# MCU_Control.net
KiCad netlist of a schematic drawn in Altium Designer
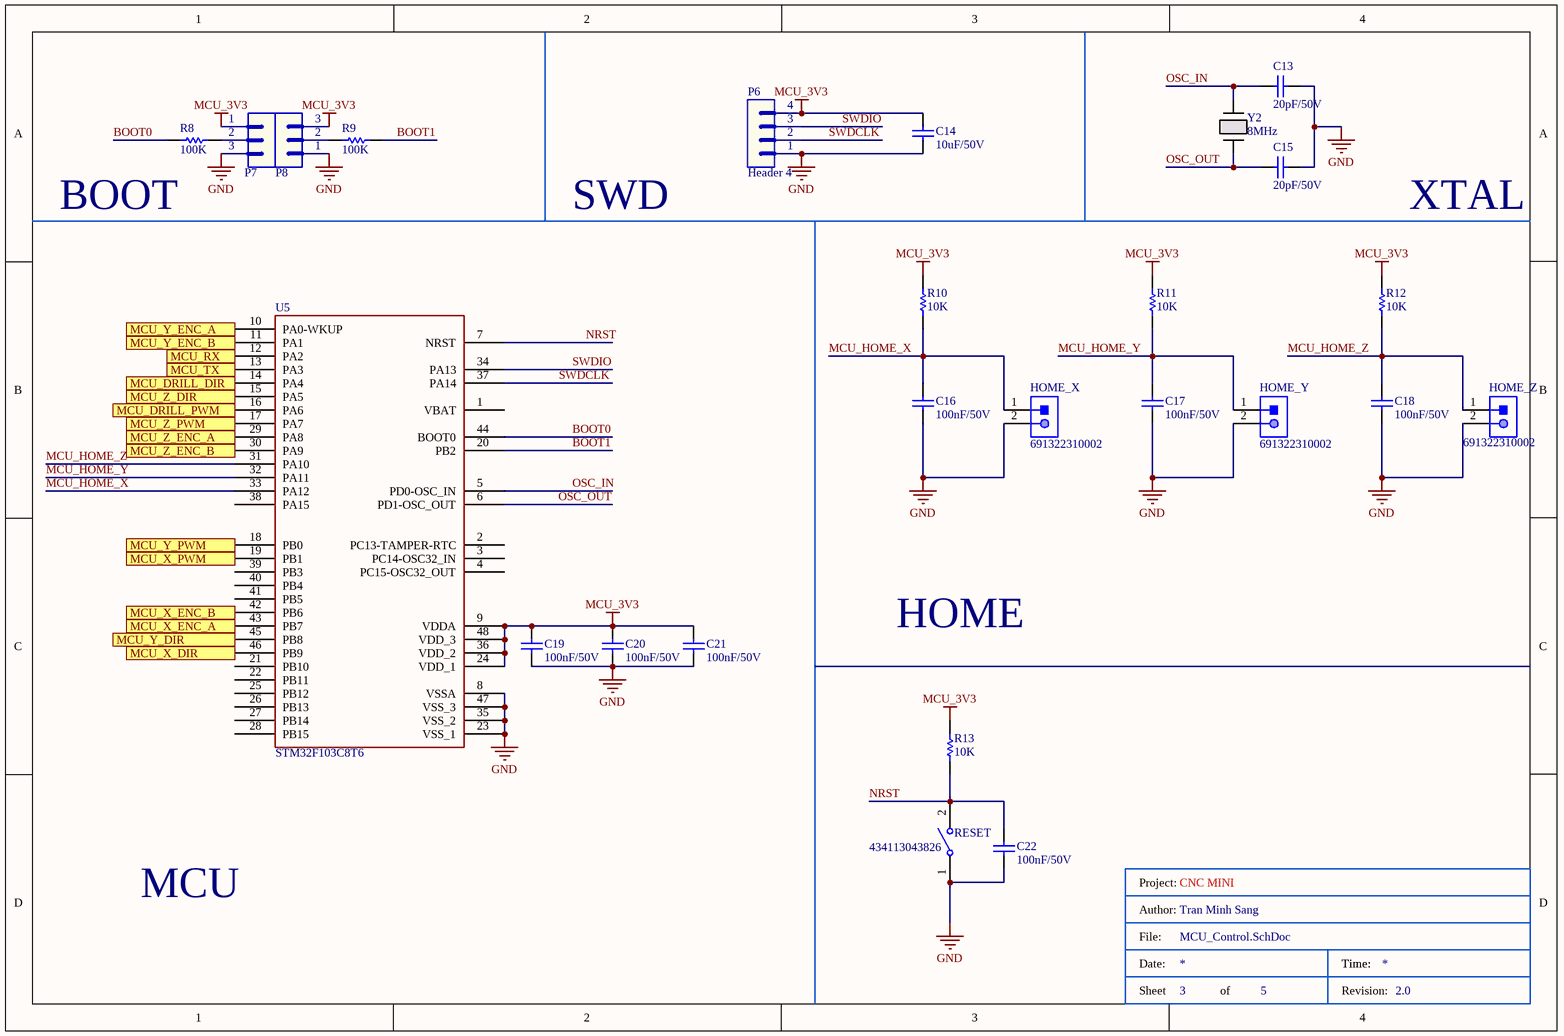
[diagram p0: MCU_Control.SchDoc]

(export (version "E")
  (design (tool "Eeschema 10.0.6"))
  (components
    (comp (ref "C13")
      (value "20pF/50V")
      (footprint "CAP-SM-0805")
      (description "CAP CER 22PF 100V X7R 0805")
      (fields
        (field (name "MANUFACTURER") "Johanson Dielectrics Inc.")
        (field (name "MANUFACTURER PART NUMBER") "101X15W102MV4E")
      )
      (libsource (lib "capacitor-smd") (part "Cap-22pF-50V-0805"))
    )
    (comp (ref "C14")
      (value "10uF/50V")
      (footprint "CAP-SM-0805")
      (description "CAP CER 10UF 50V X5R 0805")
      (fields
        (field (name "MANUFACTURER") "Yageo")
        (field (name "MANUFACTURER PART NUMBER") "CC0805KKX5R9BB106")
      )
      (libsource (lib "capacitor-smd") (part "Cap-10uF-50V-0805"))
    )
    (comp (ref "C15")
      (value "20pF/50V")
      (footprint "CAP-SM-0805")
      (description "CAP CER 22PF 100V X7R 0805")
      (fields
        (field (name "MANUFACTURER") "Johanson Dielectrics Inc.")
        (field (name "MANUFACTURER PART NUMBER") "101X15W102MV4E")
      )
      (libsource (lib "capacitor-smd") (part "Cap-22pF-50V-0805"))
    )
    (comp (ref "C16")
      (value "100nF/50V")
      (footprint "CAP-SM-0805")
      (description "CAP CER 0.1UF 50V Y5V 0805")
      (fields
        (field (name "MANUFACTURER") "Samsung Electro-Mechanics")
        (field (name "MANUFACTURER PART NUMBER") "CL21F104ZBCNNNC")
      )
      (libsource (lib "capacitor-smd") (part "Cap-100nF-50V-0805"))
    )
    (comp (ref "C17")
      (value "100nF/50V")
      (footprint "CAP-SM-0805")
      (description "CAP CER 0.1UF 50V Y5V 0805")
      (fields
        (field (name "MANUFACTURER") "Samsung Electro-Mechanics")
        (field (name "MANUFACTURER PART NUMBER") "CL21F104ZBCNNNC")
      )
      (libsource (lib "capacitor-smd") (part "Cap-100nF-50V-0805"))
    )
    (comp (ref "C18")
      (value "100nF/50V")
      (footprint "CAP-SM-0805")
      (description "CAP CER 0.1UF 50V Y5V 0805")
      (fields
        (field (name "MANUFACTURER") "Samsung Electro-Mechanics")
        (field (name "MANUFACTURER PART NUMBER") "CL21F104ZBCNNNC")
      )
      (libsource (lib "capacitor-smd") (part "Cap-100nF-50V-0805"))
    )
    (comp (ref "C19")
      (value "100nF/50V")
      (footprint "CAP-SM-0805")
      (description "CAP CER 0.1UF 50V Y5V 0805")
      (fields
        (field (name "MANUFACTURER") "Samsung Electro-Mechanics")
        (field (name "MANUFACTURER PART NUMBER") "CL21F104ZBCNNNC")
      )
      (libsource (lib "capacitor-smd") (part "Cap-100nF-50V-0805"))
    )
    (comp (ref "C20")
      (value "100nF/50V")
      (footprint "CAP-SM-0805")
      (description "CAP CER 0.1UF 50V Y5V 0805")
      (fields
        (field (name "MANUFACTURER") "Samsung Electro-Mechanics")
        (field (name "MANUFACTURER PART NUMBER") "CL21F104ZBCNNNC")
      )
      (libsource (lib "capacitor-smd") (part "Cap-100nF-50V-0805"))
    )
    (comp (ref "C21")
      (value "100nF/50V")
      (footprint "CAP-SM-0805")
      (description "CAP CER 0.1UF 50V Y5V 0805")
      (fields
        (field (name "MANUFACTURER") "Samsung Electro-Mechanics")
        (field (name "MANUFACTURER PART NUMBER") "CL21F104ZBCNNNC")
      )
      (libsource (lib "capacitor-smd") (part "Cap-100nF-50V-0805"))
    )
    (comp (ref "C22")
      (value "100nF/50V")
      (footprint "CAP-SM-0805")
      (description "CAP CER 0.1UF 50V Y5V 0805")
      (fields
        (field (name "MANUFACTURER") "Samsung Electro-Mechanics")
        (field (name "MANUFACTURER PART NUMBER") "CL21F104ZBCNNNC")
      )
      (libsource (lib "capacitor-smd") (part "Cap-100nF-50V-0805"))
    )
    (comp (ref "HOME_X")
      (value "691322310002")
      (footprint "691322310002")
      (description "WR-TBL Serie 322 Horizontal PCB Header, Pluggable, pitch 3.81mm, 2p")
      (fields (field (name "PUBLISHER") "Wurth Elektronik"))
      (libsource (lib "WR-TBL_Pluggable PCB Header") (part "691322310002"))
    )
    (comp (ref "HOME_Y")
      (value "691322310002")
      (footprint "691322310002")
      (description "WR-TBL Serie 322 Horizontal PCB Header, Pluggable, pitch 3.81mm, 2p")
      (fields (field (name "PUBLISHER") "Wurth Elektronik"))
      (libsource (lib "WR-TBL_Pluggable PCB Header") (part "691322310002"))
    )
    (comp (ref "HOME_Z")
      (value "691322310002")
      (footprint "691322310002")
      (description "WR-TBL Serie 322 Horizontal PCB Header, Pluggable, pitch 3.81mm, 2p")
      (fields (field (name "PUBLISHER") "Wurth Elektronik"))
      (libsource (lib "WR-TBL_Pluggable PCB Header") (part "691322310002"))
    )
    (comp (ref "P6")
      (value "Header 4")
      (footprint "JP4")
      (description "Header, 4-Pin")
      (fields (field (name "LOCAL SUPPLIER PART NUMBER") "x") (field (name "PUBLISHER") "Altium Limited"))
      (libsource (lib "header-connector") (part "Header 4"))
    )
    (comp (ref "P7")
      (value "Header 3")
      (footprint "JP3")
      (description "Header, 3-Pin")
      (fields (field (name "LOCAL SUPPLIER PART NUMBER") "x") (field (name "PUBLISHER") "Altium Limited"))
      (libsource (lib "header-connector") (part "Header 3"))
    )
    (comp (ref "P8")
      (value "Header 3")
      (footprint "JP3")
      (description "Header, 3-Pin")
      (fields (field (name "LOCAL SUPPLIER PART NUMBER") "x") (field (name "PUBLISHER") "Altium Limited"))
      (libsource (lib "") (part "Header 3_1"))
    )
    (comp (ref "R8")
      (value "100K")
      (footprint "resistor-smd:RES-SM-0805")
      (description "RES 0 OHM JUMPER 0805")
      (fields
        (field (name "MANUFACTURER") "Vishay Dale")
        (field (name "MANUFACTURER PART NUMBER") "WSL080500000ZEA9")
      )
      (libsource (lib "resistor-smd") (part "Res-100K-0805"))
    )
    (comp (ref "R9")
      (value "100K")
      (footprint "resistor-smd:RES-SM-0805")
      (description "RES 0 OHM JUMPER 0805")
      (fields
        (field (name "MANUFACTURER") "Vishay Dale")
        (field (name "MANUFACTURER PART NUMBER") "WSL080500000ZEA9")
      )
      (libsource (lib "resistor-smd") (part "Res-100K-0805"))
    )
    (comp (ref "R10")
      (value "10K")
      (footprint "resistor-smd:RES-SM-0805")
      (description "RES 10K OHM 1% 1/4W 0805")
      (fields
        (field (name "MANUFACTURER") "Stackpole Electronics Inc")
        (field (name "MANUFACTURER PART NUMBER") "RNCP0805FTD10K0")
      )
      (libsource (lib "resistor-smd") (part "Res-10k-0805"))
    )
    (comp (ref "R11")
      (value "10K")
      (footprint "resistor-smd:RES-SM-0805")
      (description "RES 10K OHM 1% 1/4W 0805")
      (fields
        (field (name "MANUFACTURER") "Stackpole Electronics Inc")
        (field (name "MANUFACTURER PART NUMBER") "RNCP0805FTD10K0")
      )
      (libsource (lib "resistor-smd") (part "Res-10k-0805"))
    )
    (comp (ref "R12")
      (value "10K")
      (footprint "resistor-smd:RES-SM-0805")
      (description "RES 10K OHM 1% 1/4W 0805")
      (fields
        (field (name "MANUFACTURER") "Stackpole Electronics Inc")
        (field (name "MANUFACTURER PART NUMBER") "RNCP0805FTD10K0")
      )
      (libsource (lib "resistor-smd") (part "Res-10k-0805"))
    )
    (comp (ref "R13")
      (value "10K")
      (footprint "resistor-smd:RES-SM-0805")
      (description "RES 10K OHM 1% 1/4W 0805")
      (fields
        (field (name "MANUFACTURER") "Stackpole Electronics Inc")
        (field (name "MANUFACTURER PART NUMBER") "RNCP0805FTD10K0")
      )
      (libsource (lib "resistor-smd") (part "Res-10k-0805"))
    )
    (comp (ref "RESET")
      (value "434113043826")
      (footprint "434113043826")
      (description "WS-TASV J-Bend SMT Tact Switch 6x3.5mm, height 4.3mm, 260gf")
      (fields (field (name "LOCAL SUPPLIER PART NUMBER") "x") (field (name "PUBLISHER") "Wurth Elektronik"))
      (libsource (lib "switch") (part "434113043826"))
    )
    (comp (ref "U5")
      (value "STM32F103C8T6")
      (footprint "LQFP-48")
      (fields (field (name "MANUFACTURER") "ST Electronic"))
      (libsource (lib "MiniCNC_ver2") (part "STM32F103C8T6"))
    )
    (comp (ref "Y2")
      (value "8MHz")
      (footprint "xtal2_CX5032GB_AVX-L")
      (description "No Description Available")
      (fields
        (field (name "MANUFACTURER_PART_NUMBER") "CX5032GB08000H0HEQZ1")
        (field (name "COPYRIGHT") "Copyright (C) 2023 Ultra Librarian. All rights reserved.")
      )
      (libsource (lib "MiniCNC_ver2") (part "XTAL"))
    )
  )
  (nets
    (net (code "1") (name "/BOOT0") (class "Default")
      (node (ref "R8") (pin "1") (pinfunction "1_1") (pintype "passive"))
      (node (ref "U5") (pin "44") (pinfunction "BOOT0_44") (pintype "passive"))
    )
    (net (code "2") (name "/BOOT1") (class "Default")
      (node (ref "R9") (pin "2") (pinfunction "2_2") (pintype "passive"))
      (node (ref "U5") (pin "20") (pinfunction "PB2_20") (pintype "passive"))
    )
    (net (code "3") (name "/MCU_DRILL_DIR") (class "Default")
      (node (ref "U5") (pin "14") (pinfunction "PA4_14") (pintype "passive"))
    )
    (net (code "4") (name "/MCU_DRILL_PWM") (class "Default")
      (node (ref "U5") (pin "16") (pinfunction "PA6_16") (pintype "passive"))
    )
    (net (code "5") (name "/MCU_HOME_X") (class "Default")
      (node (ref "C16") (pin "2") (pinfunction "2_2") (pintype "passive"))
      (node (ref "HOME_X") (pin "1") (pinfunction "1_1") (pintype "passive"))
      (node (ref "R10") (pin "1") (pinfunction "1_1") (pintype "passive"))
      (node (ref "U5") (pin "33") (pinfunction "PA12_33") (pintype "passive"))
    )
    (net (code "6") (name "/MCU_HOME_Y") (class "Default")
      (node (ref "C17") (pin "2") (pinfunction "2_2") (pintype "passive"))
      (node (ref "HOME_Y") (pin "1") (pinfunction "1_1") (pintype "passive"))
      (node (ref "R11") (pin "1") (pinfunction "1_1") (pintype "passive"))
      (node (ref "U5") (pin "32") (pinfunction "PA11_32") (pintype "passive"))
    )
    (net (code "7") (name "/MCU_HOME_Z") (class "Default")
      (node (ref "C18") (pin "2") (pinfunction "2_2") (pintype "passive"))
      (node (ref "HOME_Z") (pin "1") (pinfunction "1_1") (pintype "passive"))
      (node (ref "R12") (pin "1") (pinfunction "1_1") (pintype "passive"))
      (node (ref "U5") (pin "31") (pinfunction "PA10_31") (pintype "passive"))
    )
    (net (code "8") (name "/MCU_RX") (class "Default")
      (node (ref "U5") (pin "12") (pinfunction "PA2_12") (pintype "passive"))
    )
    (net (code "9") (name "/MCU_TX") (class "Default")
      (node (ref "U5") (pin "13") (pinfunction "PA3_13") (pintype "passive"))
    )
    (net (code "10") (name "/MCU_X_DIR") (class "Default")
      (node (ref "U5") (pin "46") (pinfunction "PB9_46") (pintype "passive"))
    )
    (net (code "11") (name "/MCU_X_ENC_A") (class "Default")
      (node (ref "U5") (pin "43") (pinfunction "PB7_43") (pintype "passive"))
    )
    (net (code "12") (name "/MCU_X_ENC_B") (class "Default")
      (node (ref "U5") (pin "42") (pinfunction "PB6_42") (pintype "passive"))
    )
    (net (code "13") (name "/MCU_X_PWM") (class "Default")
      (node (ref "U5") (pin "19") (pinfunction "PB1_19") (pintype "passive"))
    )
    (net (code "14") (name "/MCU_Y_DIR") (class "Default")
      (node (ref "U5") (pin "45") (pinfunction "PB8_45") (pintype "passive"))
    )
    (net (code "15") (name "/MCU_Y_ENC_A") (class "Default")
      (node (ref "U5") (pin "10") (pinfunction "PA0-WKUP_10") (pintype "passive"))
    )
    (net (code "16") (name "/MCU_Y_ENC_B") (class "Default")
      (node (ref "U5") (pin "11") (pinfunction "PA1_11") (pintype "passive"))
    )
    (net (code "17") (name "/MCU_Y_PWM") (class "Default")
      (node (ref "U5") (pin "18") (pinfunction "PB0_18") (pintype "passive"))
    )
    (net (code "18") (name "/MCU_Z_DIR") (class "Default")
      (node (ref "U5") (pin "15") (pinfunction "PA5_15") (pintype "passive"))
    )
    (net (code "19") (name "/MCU_Z_ENC_A") (class "Default")
      (node (ref "U5") (pin "29") (pinfunction "PA8_29") (pintype "passive"))
    )
    (net (code "20") (name "/MCU_Z_ENC_B") (class "Default")
      (node (ref "U5") (pin "30") (pinfunction "PA9_30") (pintype "passive"))
    )
    (net (code "21") (name "/MCU_Z_PWM") (class "Default")
      (node (ref "U5") (pin "17") (pinfunction "PA7_17") (pintype "passive"))
    )
    (net (code "22") (name "/NRST") (class "Default")
      (node (ref "C22") (pin "2") (pinfunction "2_2") (pintype "passive"))
      (node (ref "R13") (pin "1") (pinfunction "1_1") (pintype "passive"))
      (node (ref "RESET") (pin "2") (pinfunction "2_2") (pintype "passive"))
      (node (ref "U5") (pin "7") (pinfunction "NRST_7") (pintype "passive"))
    )
    (net (code "23") (name "/OSC_IN") (class "Default")
      (node (ref "C13") (pin "2") (pinfunction "2_2") (pintype "passive"))
      (node (ref "U5") (pin "5") (pinfunction "PD0-OSC_IN_5") (pintype "passive"))
      (node (ref "Y2") (pin "1") (pinfunction "1_1") (pintype "passive"))
    )
    (net (code "24") (name "/OSC_OUT") (class "Default")
      (node (ref "C15") (pin "2") (pinfunction "2_2") (pintype "passive"))
      (node (ref "U5") (pin "6") (pinfunction "PD1-OSC_OUT_6") (pintype "passive"))
      (node (ref "Y2") (pin "2") (pinfunction "2_2") (pintype "passive"))
    )
    (net (code "25") (name "/SWDCLK") (class "Default")
      (node (ref "P6") (pin "2") (pinfunction "2_2") (pintype "passive"))
      (node (ref "U5") (pin "37") (pinfunction "PA14_37") (pintype "passive"))
    )
    (net (code "26") (name "/SWDIO") (class "Default")
      (node (ref "P6") (pin "3") (pinfunction "3_3") (pintype "passive"))
      (node (ref "U5") (pin "34") (pinfunction "PA13_34") (pintype "passive"))
    )
    (net (code "27") (name "GND") (class "Default")
      (node (ref "C13") (pin "1") (pinfunction "1_1") (pintype "passive"))
      (node (ref "C14") (pin "1") (pinfunction "1_1") (pintype "passive"))
      (node (ref "C15") (pin "1") (pinfunction "1_1") (pintype "passive"))
      (node (ref "C16") (pin "1") (pinfunction "1_1") (pintype "passive"))
      (node (ref "C17") (pin "1") (pinfunction "1_1") (pintype "passive"))
      (node (ref "C18") (pin "1") (pinfunction "1_1") (pintype "passive"))
      (node (ref "C19") (pin "2") (pinfunction "2_2") (pintype "passive"))
      (node (ref "C20") (pin "2") (pinfunction "2_2") (pintype "passive"))
      (node (ref "C21") (pin "2") (pinfunction "2_2") (pintype "passive"))
      (node (ref "C22") (pin "1") (pinfunction "1_1") (pintype "passive"))
      (node (ref "HOME_X") (pin "2") (pinfunction "2_2") (pintype "passive"))
      (node (ref "HOME_Y") (pin "2") (pinfunction "2_2") (pintype "passive"))
      (node (ref "HOME_Z") (pin "2") (pinfunction "2_2") (pintype "passive"))
      (node (ref "P6") (pin "1") (pinfunction "1_1") (pintype "passive"))
      (node (ref "P7") (pin "3") (pinfunction "3_3") (pintype "passive"))
      (node (ref "P8") (pin "1") (pinfunction "1_1") (pintype "passive"))
      (node (ref "RESET") (pin "1") (pinfunction "1_1") (pintype "passive"))
      (node (ref "U5") (pin "23") (pinfunction "VSS_1_23") (pintype "passive"))
      (node (ref "U5") (pin "35") (pinfunction "VSS_2_35") (pintype "passive"))
      (node (ref "U5") (pin "47") (pinfunction "VSS_3_47") (pintype "passive"))
      (node (ref "U5") (pin "8") (pinfunction "VSSA_8") (pintype "passive"))
    )
    (net (code "28") (name "MCU_3V3") (class "Default")
      (node (ref "C14") (pin "2") (pinfunction "2_2") (pintype "passive"))
      (node (ref "C19") (pin "1") (pinfunction "1_1") (pintype "passive"))
      (node (ref "C20") (pin "1") (pinfunction "1_1") (pintype "passive"))
      (node (ref "C21") (pin "1") (pinfunction "1_1") (pintype "passive"))
      (node (ref "P6") (pin "4") (pinfunction "4_4") (pintype "passive"))
      (node (ref "P7") (pin "1") (pinfunction "1_1") (pintype "passive"))
      (node (ref "P8") (pin "3") (pinfunction "3_3") (pintype "passive"))
      (node (ref "R10") (pin "2") (pinfunction "2_2") (pintype "passive"))
      (node (ref "R11") (pin "2") (pinfunction "2_2") (pintype "passive"))
      (node (ref "R12") (pin "2") (pinfunction "2_2") (pintype "passive"))
      (node (ref "R13") (pin "2") (pinfunction "2_2") (pintype "passive"))
      (node (ref "U5") (pin "24") (pinfunction "VDD_1_24") (pintype "passive"))
      (node (ref "U5") (pin "36") (pinfunction "VDD_2_36") (pintype "passive"))
      (node (ref "U5") (pin "48") (pinfunction "VDD_3_48") (pintype "passive"))
      (node (ref "U5") (pin "9") (pinfunction "VDDA_9") (pintype "passive"))
    )
    (net (code "29") (name "Net-(P7-Pad2)") (class "Default")
      (node (ref "P7") (pin "2") (pinfunction "2_2") (pintype "passive"))
      (node (ref "R8") (pin "2") (pinfunction "2_2") (pintype "passive"))
    )
    (net (code "30") (name "Net-(P8-Pad2)") (class "Default")
      (node (ref "P8") (pin "2") (pinfunction "2_2") (pintype "passive"))
      (node (ref "R9") (pin "1") (pinfunction "1_1") (pintype "passive"))
    )
    (net (code "31") (name "unconnected-(U5-PA15-Pad38)") (class "Default")
      (node (ref "U5") (pin "38") (pinfunction "PA15_38") (pintype "passive"))
    )
    (net (code "32") (name "unconnected-(U5-PB3-Pad39)") (class "Default")
      (node (ref "U5") (pin "39") (pinfunction "PB3_39") (pintype "passive"))
    )
    (net (code "33") (name "unconnected-(U5-PB4-Pad40)") (class "Default")
      (node (ref "U5") (pin "40") (pinfunction "PB4_40") (pintype "passive"))
    )
    (net (code "34") (name "unconnected-(U5-PB5-Pad41)") (class "Default")
      (node (ref "U5") (pin "41") (pinfunction "PB5_41") (pintype "passive"))
    )
    (net (code "35") (name "unconnected-(U5-PB10-Pad21)") (class "Default")
      (node (ref "U5") (pin "21") (pinfunction "PB10_21") (pintype "passive"))
    )
    (net (code "36") (name "unconnected-(U5-PB11-Pad22)") (class "Default")
      (node (ref "U5") (pin "22") (pinfunction "PB11_22") (pintype "passive"))
    )
    (net (code "37") (name "unconnected-(U5-PB12-Pad25)") (class "Default")
      (node (ref "U5") (pin "25") (pinfunction "PB12_25") (pintype "passive"))
    )
    (net (code "38") (name "unconnected-(U5-PB13-Pad26)") (class "Default")
      (node (ref "U5") (pin "26") (pinfunction "PB13_26") (pintype "passive"))
    )
    (net (code "39") (name "unconnected-(U5-PB14-Pad27)") (class "Default")
      (node (ref "U5") (pin "27") (pinfunction "PB14_27") (pintype "passive"))
    )
    (net (code "40") (name "unconnected-(U5-PB15-Pad28)") (class "Default")
      (node (ref "U5") (pin "28") (pinfunction "PB15_28") (pintype "passive"))
    )
    (net (code "41") (name "unconnected-(U5-PC13-TAMPER-RTC-Pad2)") (class "Default")
      (node (ref "U5") (pin "2") (pinfunction "PC13-TAMPER-RTC_2") (pintype "passive"))
    )
    (net (code "42") (name "unconnected-(U5-PC14-OSC32_IN-Pad3)") (class "Default")
      (node (ref "U5") (pin "3") (pinfunction "PC14-OSC32_IN_3") (pintype "passive"))
    )
    (net (code "43") (name "unconnected-(U5-PC15-OSC32_OUT-Pad4)") (class "Default")
      (node (ref "U5") (pin "4") (pinfunction "PC15-OSC32_OUT_4") (pintype "passive"))
    )
    (net (code "44") (name "unconnected-(U5-VBAT-Pad1)") (class "Default")
      (node (ref "U5") (pin "1") (pinfunction "VBAT_1") (pintype "passive"))
    )
  )
)
